# Multiplexer.net
KiCad netlist of a schematic drawn in Altium Designer
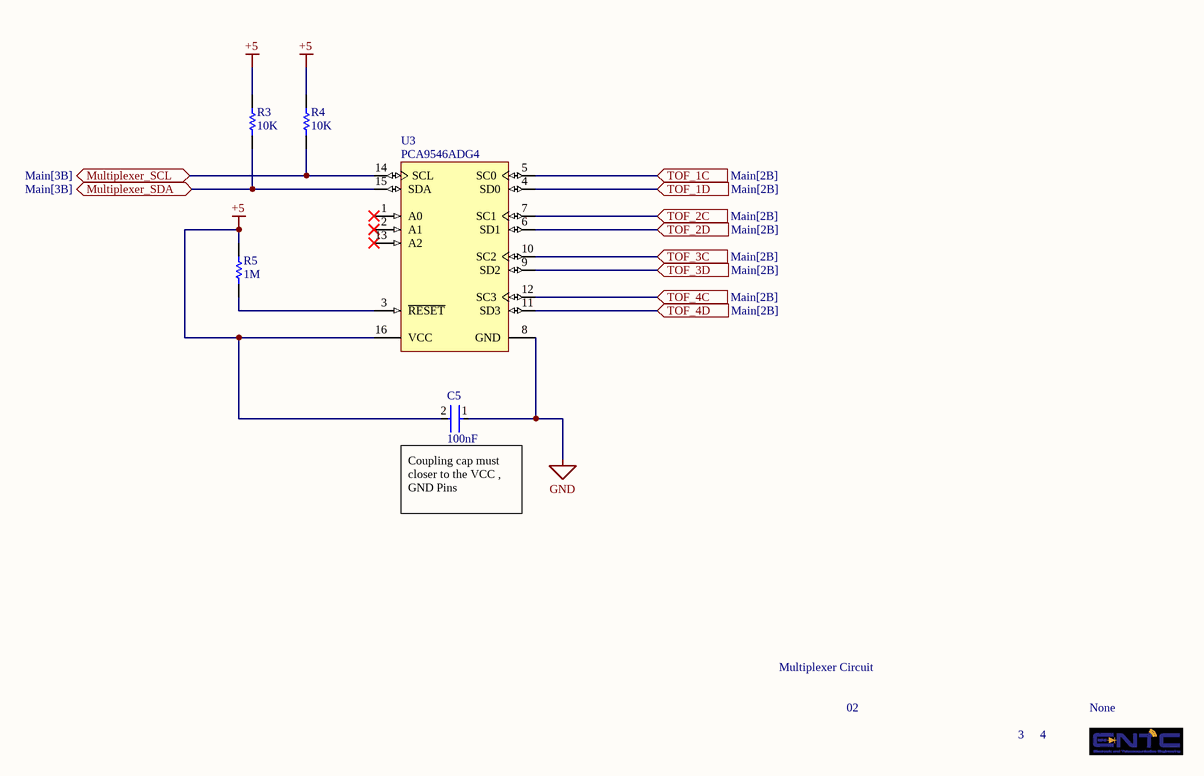
[diagram p0: Multiplexer.SchDoc]

(export (version "E")
  (design (tool "Eeschema 10.0.6"))
  (components
    (comp (ref "C5")
      (value "100nF")
      (footprint "FP-C1206C-EB-MFG")
      (description "CAP CER 0.1UF 200V 10% X7R 1206")
      (fields (field (name "TOLERANCE") "0.1") (field (name "MANUFACTURER PART NUMBER") "C1206C104K2RACTU"))
      (libsource (lib "Altium Content Vault") (part "b4654b650e69147ec39a6b967a45e02"))
    )
    (comp (ref "R3")
      (value "10K")
      (footprint "RESC2013X60X35ML10T20")
      (fields (field (name "TOLERANCE") "5%") (field (name "MANUFACTURER") "Yageo"))
      (libsource (lib "Altium Content Vault") (part "RES-2"))
    )
    (comp (ref "R4")
      (value "10K")
      (footprint "RESC2013X60X35ML10T20")
      (fields (field (name "TOLERANCE") "5%") (field (name "MANUFACTURER") "Yageo"))
      (libsource (lib "Altium Content Vault") (part "RES-2"))
    )
    (comp (ref "R5")
      (value "1M")
      (footprint "RESC2013X60X35ML10T20")
      (fields (field (name "TOLERANCE") "5%") (field (name "MANUFACTURER") "Yageo"))
      (libsource (lib "Altium Content Vault") (part "RES-2"))
    )
    (comp (ref "U3")
      (value "PCA9546ADG4")
      (footprint "D16_M")
      (fields (field (name "MANUFACTURER") "Texas Instruments"))
      (libsource (lib "Altium Content Vault") (part "TI-PCA9546A-SOIC_D-16"))
    )
  )
  (nets
    (net (code "1") (name "+5") (class "Default")
      (node (ref "C5") (pin "2") (pinfunction "2_2") (pintype "passive"))
      (node (ref "R3") (pin "2") (pinfunction "2_2") (pintype "passive"))
      (node (ref "R4") (pin "2") (pinfunction "2_2") (pintype "passive"))
      (node (ref "R5") (pin "2") (pinfunction "2_2") (pintype "passive"))
      (node (ref "U3") (pin "16") (pinfunction "VCC_16") (pintype "power_in"))
    )
    (net (code "2") (name "/Multiplexer_SCL") (class "Default")
      (node (ref "R4") (pin "1") (pinfunction "1_1") (pintype "passive"))
      (node (ref "U3") (pin "14") (pinfunction "SCL_14") (pintype "bidirectional"))
    )
    (net (code "3") (name "/Multiplexer_SDA") (class "Default")
      (node (ref "R3") (pin "1") (pinfunction "1_1") (pintype "passive"))
      (node (ref "U3") (pin "15") (pinfunction "SDA_15") (pintype "bidirectional"))
    )
    (net (code "4") (name "/TOF_1C") (class "Default")
      (node (ref "U3") (pin "5") (pinfunction "SC0_5") (pintype "bidirectional"))
    )
    (net (code "5") (name "/TOF_1D") (class "Default")
      (node (ref "U3") (pin "4") (pinfunction "SD0_4") (pintype "bidirectional"))
    )
    (net (code "6") (name "/TOF_2C") (class "Default")
      (node (ref "U3") (pin "7") (pinfunction "SC1_7") (pintype "bidirectional"))
    )
    (net (code "7") (name "/TOF_2D") (class "Default")
      (node (ref "U3") (pin "6") (pinfunction "SD1_6") (pintype "bidirectional"))
    )
    (net (code "8") (name "/TOF_3C") (class "Default")
      (node (ref "U3") (pin "10") (pinfunction "SC2_10") (pintype "bidirectional"))
    )
    (net (code "9") (name "/TOF_3D") (class "Default")
      (node (ref "U3") (pin "9") (pinfunction "SD2_9") (pintype "bidirectional"))
    )
    (net (code "10") (name "/TOF_4C") (class "Default")
      (node (ref "U3") (pin "12") (pinfunction "SC3_12") (pintype "bidirectional"))
    )
    (net (code "11") (name "/TOF_4D") (class "Default")
      (node (ref "U3") (pin "11") (pinfunction "SD3_11") (pintype "bidirectional"))
    )
    (net (code "12") (name "GND") (class "Default")
      (node (ref "C5") (pin "1") (pinfunction "1_1") (pintype "passive"))
      (node (ref "U3") (pin "8") (pinfunction "GND_8") (pintype "power_in"))
    )
    (net (code "13") (name "Net-(U3-~{RESET})") (class "Default")
      (node (ref "R5") (pin "1") (pinfunction "1_1") (pintype "passive"))
      (node (ref "U3") (pin "3") (pinfunction "~{RESET}_3") (pintype "input"))
    )
    (net (code "14") (name "unconnected-(U3-A0-Pad1)") (class "Default")
      (node (ref "U3") (pin "1") (pinfunction "A0_1") (pintype "input+no_connect"))
    )
    (net (code "15") (name "unconnected-(U3-A1-Pad2)") (class "Default")
      (node (ref "U3") (pin "2") (pinfunction "A1_2") (pintype "input+no_connect"))
    )
    (net (code "16") (name "unconnected-(U3-A2-Pad13)") (class "Default")
      (node (ref "U3") (pin "13") (pinfunction "A2_13") (pintype "input+no_connect"))
    )
  )
)
